# IDS_ADC_SMT.net
KiCad netlist of a schematic drawn in EAGLE
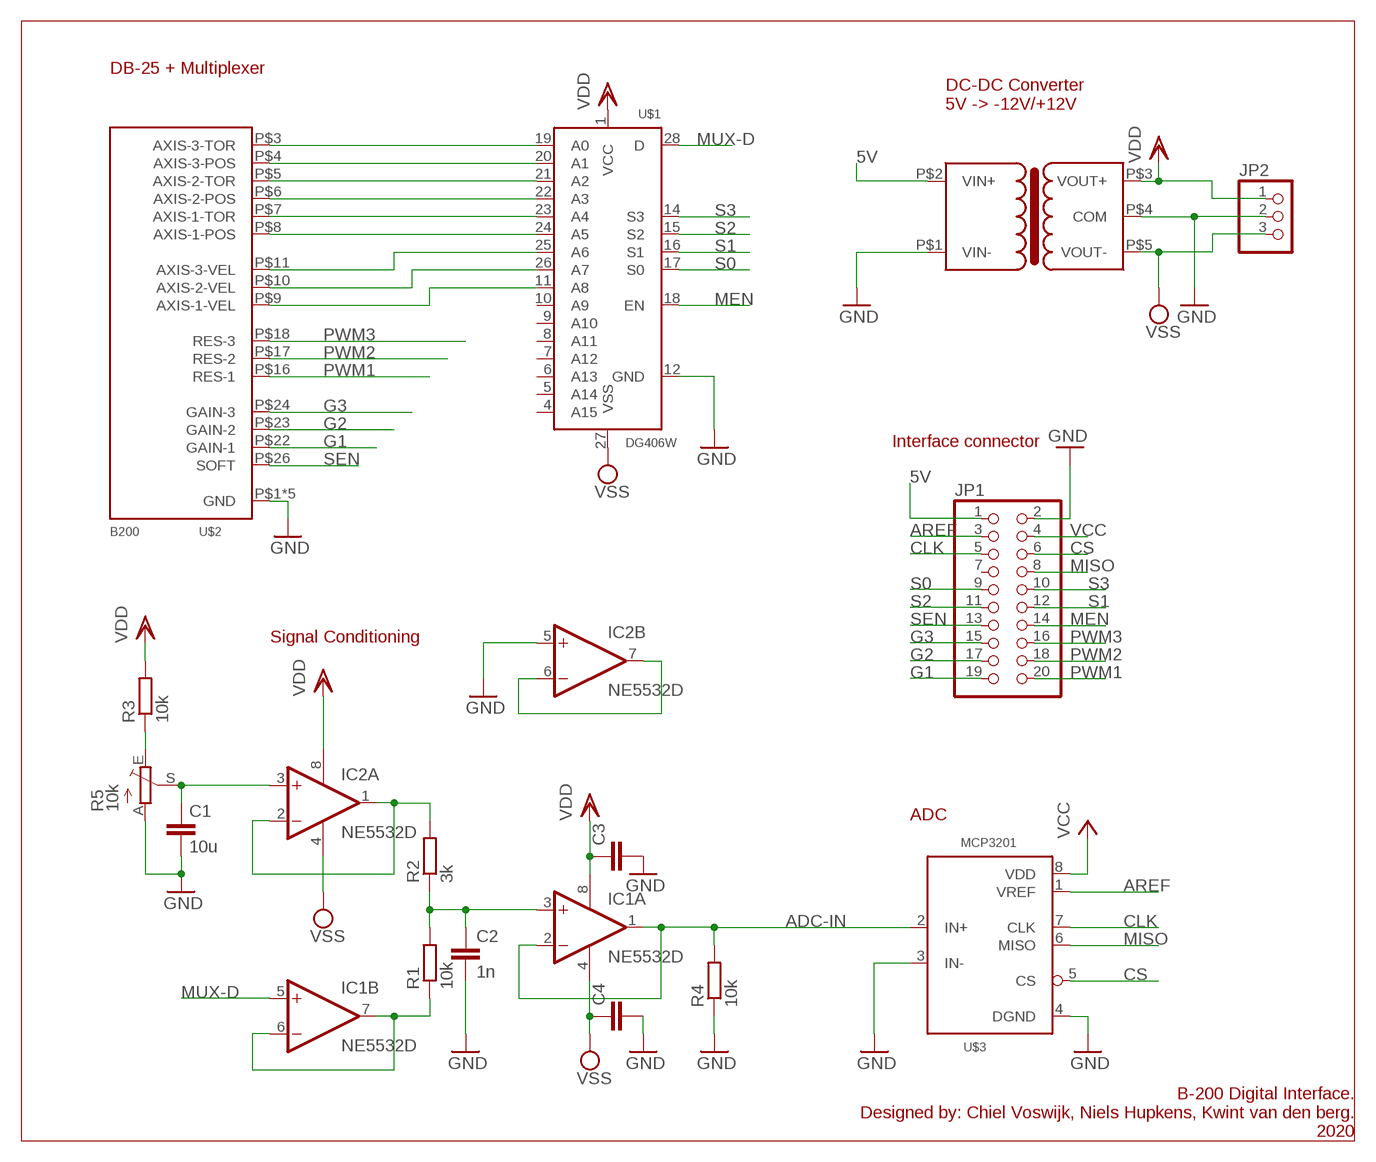
[diagram p0: schematic, sheet 1]

(export (version "E")
  (design (tool "Eeschema 10.0.6"))
  (components
    (comp (ref "C1")
      (value "10u")
      (footprint "eagle-import:C1210")
      (libsource (lib "eagle-import") (part "C-EUC1210"))
    )
    (comp (ref "C2")
      (value "1n")
      (footprint "eagle-import:C0805")
      (libsource (lib "eagle-import") (part "C-EUC0805"))
    )
    (comp (ref "C3")
      (value "C-EUC0805")
      (footprint "eagle-import:C0805")
      (libsource (lib "eagle-import") (part "C-EUC0805"))
    )
    (comp (ref "C4")
      (value "C-EUC0805")
      (footprint "eagle-import:C0805")
      (libsource (lib "eagle-import") (part "C-EUC0805"))
    )
    (comp (ref "IC1")
      (value "NE5532D")
      (footprint "eagle-import:SO08")
      (libsource (lib "eagle-import") (part "NE5532D"))
    )
    (comp (ref "IC2")
      (value "NE5532D")
      (footprint "eagle-import:SO08")
      (libsource (lib "eagle-import") (part "NE5532D"))
    )
    (comp (ref "JP1")
      (value "PINHD-2X10")
      (footprint "eagle-import:2X10")
      (libsource (lib "eagle-import") (part "PINHD-2X10"))
    )
    (comp (ref "JP2")
      (value "PINHD-1X3")
      (footprint "eagle-import:1X03")
      (libsource (lib "eagle-import") (part "PINHD-1X3"))
    )
    (comp (ref "R1")
      (value "10k")
      (footprint "eagle-import:R0805")
      (libsource (lib "eagle-import") (part "R-EU_R0805"))
    )
    (comp (ref "R2")
      (value "3k")
      (footprint "eagle-import:R0805")
      (libsource (lib "eagle-import") (part "R-EU_R0805"))
    )
    (comp (ref "R3")
      (value "10k")
      (footprint "eagle-import:R0805")
      (libsource (lib "eagle-import") (part "R-EU_R0805"))
    )
    (comp (ref "R4")
      (value "10k")
      (footprint "eagle-import:R0805")
      (libsource (lib "eagle-import") (part "R-EU_R0805"))
    )
    (comp (ref "R5")
      (value "10k")
      (footprint "eagle-import:RJ9W")
      (libsource (lib "eagle-import") (part "TRIM_EU-RJ9W"))
    )
    (comp (ref "U$1")
      (value "DG406W")
      (footprint "eagle-import:SO-28W")
      (libsource (lib "eagle-import") (part "DG406W"))
    )
    (comp (ref "U$2")
      (value "B200")
      (footprint "eagle-import:PARALLEL")
      (libsource (lib "eagle-import") (part "B200"))
    )
    (comp (ref "U$3")
      (value "MCP3201")
      (footprint "eagle-import:DIL08")
      (libsource (lib "eagle-import") (part "MCP3201"))
    )
    (comp (ref "U$4")
      (value "TRACO-DR-NE")
      (footprint "eagle-import:TRACO-DCDC-SIP6")
      (libsource (lib "eagle-import") (part "TRACO-DR-NE"))
    )
  )
  (nets
    (net (code "1") (name "/5V") (class "Default")
      (node (ref "JP1") (pin "1") (pinfunction "1_1") (pintype "passive"))
      (node (ref "U$4") (pin "P$2") (pinfunction "VIN+_P$2") (pintype "bidirectional"))
    )
    (net (code "2") (name "/ADC-IN") (class "Default")
      (node (ref "IC1") (pin "1") (pinfunction "OUT_1") (pintype "output"))
      (node (ref "IC1") (pin "2") (pinfunction "-IN_2") (pintype "input"))
      (node (ref "R4") (pin "2") (pinfunction "2_2") (pintype "passive"))
      (node (ref "U$3") (pin "2") (pinfunction "IN+_2") (pintype "input"))
    )
    (net (code "3") (name "/AREF") (class "Default")
      (node (ref "JP1") (pin "3") (pinfunction "3_3") (pintype "passive"))
      (node (ref "U$3") (pin "1") (pinfunction "VREF_1") (pintype "bidirectional"))
    )
    (net (code "4") (name "/CLK") (class "Default")
      (node (ref "JP1") (pin "5") (pinfunction "5_5") (pintype "passive"))
      (node (ref "U$3") (pin "7") (pinfunction "CLK_7") (pintype "bidirectional"))
    )
    (net (code "5") (name "/CS") (class "Default")
      (node (ref "JP1") (pin "6") (pinfunction "6_6") (pintype "passive"))
      (node (ref "U$3") (pin "5") (pinfunction "CS_5") (pintype "bidirectional"))
    )
    (net (code "6") (name "/G1") (class "Default")
      (node (ref "JP1") (pin "19") (pinfunction "19_19") (pintype "passive"))
      (node (ref "U$2") (pin "P$22") (pinfunction "GAIN-1_P$22") (pintype "output"))
    )
    (net (code "7") (name "/G2") (class "Default")
      (node (ref "JP1") (pin "17") (pinfunction "17_17") (pintype "passive"))
      (node (ref "U$2") (pin "P$23") (pinfunction "GAIN-2_P$23") (pintype "output"))
    )
    (net (code "8") (name "/G3") (class "Default")
      (node (ref "JP1") (pin "15") (pinfunction "15_15") (pintype "passive"))
      (node (ref "U$2") (pin "P$24") (pinfunction "GAIN-3_P$24") (pintype "output"))
    )
    (net (code "9") (name "/MEN") (class "Default")
      (node (ref "JP1") (pin "14") (pinfunction "14_14") (pintype "passive"))
      (node (ref "U$1") (pin "18") (pinfunction "EN_18") (pintype "input"))
    )
    (net (code "10") (name "/MISO") (class "Default")
      (node (ref "JP1") (pin "8") (pinfunction "8_8") (pintype "passive"))
      (node (ref "U$3") (pin "6") (pinfunction "MISO_6") (pintype "bidirectional"))
    )
    (net (code "11") (name "/MUX-D") (class "Default")
      (node (ref "IC1") (pin "5") (pinfunction "+IN_5") (pintype "input"))
      (node (ref "U$1") (pin "28") (pinfunction "D_28") (pintype "bidirectional"))
    )
    (net (code "12") (name "/PWM1") (class "Default")
      (node (ref "JP1") (pin "20") (pinfunction "20_20") (pintype "passive"))
      (node (ref "U$2") (pin "P$16") (pinfunction "RES-1_P$16") (pintype "output"))
    )
    (net (code "13") (name "/PWM2") (class "Default")
      (node (ref "JP1") (pin "18") (pinfunction "18_18") (pintype "passive"))
      (node (ref "U$2") (pin "P$17") (pinfunction "RES-2_P$17") (pintype "output"))
    )
    (net (code "14") (name "/PWM3") (class "Default")
      (node (ref "JP1") (pin "16") (pinfunction "16_16") (pintype "passive"))
      (node (ref "U$2") (pin "P$18") (pinfunction "RES-3_P$18") (pintype "output"))
    )
    (net (code "15") (name "/S0") (class "Default")
      (node (ref "JP1") (pin "9") (pinfunction "9_9") (pintype "passive"))
      (node (ref "U$1") (pin "17") (pinfunction "S0_17") (pintype "input"))
    )
    (net (code "16") (name "/S1") (class "Default")
      (node (ref "JP1") (pin "12") (pinfunction "12_12") (pintype "passive"))
      (node (ref "U$1") (pin "16") (pinfunction "S1_16") (pintype "input"))
    )
    (net (code "17") (name "/S2") (class "Default")
      (node (ref "JP1") (pin "11") (pinfunction "11_11") (pintype "passive"))
      (node (ref "U$1") (pin "15") (pinfunction "S2_15") (pintype "input"))
    )
    (net (code "18") (name "/S3") (class "Default")
      (node (ref "JP1") (pin "10") (pinfunction "10_10") (pintype "passive"))
      (node (ref "U$1") (pin "14") (pinfunction "S3_14") (pintype "input"))
    )
    (net (code "19") (name "/SEN") (class "Default")
      (node (ref "JP1") (pin "13") (pinfunction "13_13") (pintype "passive"))
      (node (ref "U$2") (pin "P$26") (pinfunction "SOFT_P$26") (pintype "output"))
    )
    (net (code "20") (name "GND") (class "Default")
      (node (ref "C1") (pin "2") (pinfunction "2_2") (pintype "passive"))
      (node (ref "C2") (pin "2") (pinfunction "2_2") (pintype "passive"))
      (node (ref "C3") (pin "2") (pinfunction "2_2") (pintype "passive"))
      (node (ref "C4") (pin "2") (pinfunction "2_2") (pintype "passive"))
      (node (ref "IC2") (pin "5") (pinfunction "+IN_5") (pintype "input"))
      (node (ref "JP1") (pin "2") (pinfunction "2_2") (pintype "passive"))
      (node (ref "JP2") (pin "2") (pinfunction "2_2") (pintype "passive"))
      (node (ref "R4") (pin "1") (pinfunction "1_1") (pintype "passive"))
      (node (ref "R5") (pin "A") (pinfunction "A_A") (pintype "passive"))
      (node (ref "U$1") (pin "12") (pinfunction "GND_12") (pintype "open_collector"))
      (node (ref "U$2") (pin "P$1") (pinfunction "GND_P$1") (pintype "output"))
      (node (ref "U$2") (pin "P$19") (pinfunction "GND_P$19") (pintype "output"))
      (node (ref "U$2") (pin "P$2") (pinfunction "GND_P$2") (pintype "output"))
      (node (ref "U$2") (pin "P$20") (pinfunction "GND_P$20") (pintype "output"))
      (node (ref "U$2") (pin "P$21") (pinfunction "GND_P$21") (pintype "output"))
      (node (ref "U$3") (pin "3") (pinfunction "IN-_3") (pintype "input"))
      (node (ref "U$3") (pin "4") (pinfunction "DGND_4") (pintype "power_in"))
      (node (ref "U$4") (pin "P$1") (pinfunction "VIN-_P$1") (pintype "bidirectional"))
      (node (ref "U$4") (pin "P$4") (pinfunction "COM_P$4") (pintype "bidirectional"))
    )
    (net (code "21") (name "Net-(IC1A-+IN)") (class "Default")
      (node (ref "C2") (pin "1") (pinfunction "1_1") (pintype "passive"))
      (node (ref "IC1") (pin "3") (pinfunction "+IN_3") (pintype "input"))
      (node (ref "R1") (pin "2") (pinfunction "2_2") (pintype "passive"))
      (node (ref "R2") (pin "1") (pinfunction "1_1") (pintype "passive"))
    )
    (net (code "22") (name "Net-(IC1B--IN)") (class "Default")
      (node (ref "IC1") (pin "6") (pinfunction "-IN_6") (pintype "input"))
      (node (ref "IC1") (pin "7") (pinfunction "OUT_7") (pintype "output"))
      (node (ref "R1") (pin "1") (pinfunction "1_1") (pintype "passive"))
    )
    (net (code "23") (name "Net-(IC2A-+IN)") (class "Default")
      (node (ref "C1") (pin "1") (pinfunction "1_1") (pintype "passive"))
      (node (ref "IC2") (pin "3") (pinfunction "+IN_3") (pintype "input"))
      (node (ref "R5") (pin "S") (pinfunction "S_S") (pintype "passive"))
    )
    (net (code "24") (name "Net-(IC2A--IN)") (class "Default")
      (node (ref "IC2") (pin "1") (pinfunction "OUT_1") (pintype "output"))
      (node (ref "IC2") (pin "2") (pinfunction "-IN_2") (pintype "input"))
      (node (ref "R2") (pin "2") (pinfunction "2_2") (pintype "passive"))
    )
    (net (code "25") (name "Net-(IC2B--IN)") (class "Default")
      (node (ref "IC2") (pin "6") (pinfunction "-IN_6") (pintype "input"))
      (node (ref "IC2") (pin "7") (pinfunction "OUT_7") (pintype "output"))
    )
    (net (code "26") (name "Net-(R3-Pad1)") (class "Default")
      (node (ref "R3") (pin "1") (pinfunction "1_1") (pintype "passive"))
      (node (ref "R5") (pin "E") (pinfunction "E_E") (pintype "passive"))
    )
    (net (code "27") (name "Net-(U$1-A0)") (class "Default")
      (node (ref "U$1") (pin "19") (pinfunction "A0_19") (pintype "bidirectional"))
      (node (ref "U$2") (pin "P$3") (pinfunction "AXIS-3-TOR_P$3") (pintype "output"))
    )
    (net (code "28") (name "Net-(U$1-A1)") (class "Default")
      (node (ref "U$1") (pin "20") (pinfunction "A1_20") (pintype "bidirectional"))
      (node (ref "U$2") (pin "P$4") (pinfunction "AXIS-3-POS_P$4") (pintype "output"))
    )
    (net (code "29") (name "Net-(U$1-A2)") (class "Default")
      (node (ref "U$1") (pin "21") (pinfunction "A2_21") (pintype "bidirectional"))
      (node (ref "U$2") (pin "P$5") (pinfunction "AXIS-2-TOR_P$5") (pintype "output"))
    )
    (net (code "30") (name "Net-(U$1-A3)") (class "Default")
      (node (ref "U$1") (pin "22") (pinfunction "A3_22") (pintype "bidirectional"))
      (node (ref "U$2") (pin "P$6") (pinfunction "AXIS-2-POS_P$6") (pintype "output"))
    )
    (net (code "31") (name "Net-(U$1-A4)") (class "Default")
      (node (ref "U$1") (pin "23") (pinfunction "A4_23") (pintype "bidirectional"))
      (node (ref "U$2") (pin "P$7") (pinfunction "AXIS-1-TOR_P$7") (pintype "output"))
    )
    (net (code "32") (name "Net-(U$1-A5)") (class "Default")
      (node (ref "U$1") (pin "24") (pinfunction "A5_24") (pintype "bidirectional"))
      (node (ref "U$2") (pin "P$8") (pinfunction "AXIS-1-POS_P$8") (pintype "output"))
    )
    (net (code "33") (name "Net-(U$1-A6)") (class "Default")
      (node (ref "U$1") (pin "25") (pinfunction "A6_25") (pintype "bidirectional"))
      (node (ref "U$2") (pin "P$11") (pinfunction "AXIS-3-VEL_P$11") (pintype "output"))
    )
    (net (code "34") (name "Net-(U$1-A7)") (class "Default")
      (node (ref "U$1") (pin "26") (pinfunction "A7_26") (pintype "bidirectional"))
      (node (ref "U$2") (pin "P$10") (pinfunction "AXIS-2-VEL_P$10") (pintype "output"))
    )
    (net (code "35") (name "Net-(U$1-A8)") (class "Default")
      (node (ref "U$1") (pin "11") (pinfunction "A8_11") (pintype "bidirectional"))
      (node (ref "U$2") (pin "P$9") (pinfunction "AXIS-1-VEL_P$9") (pintype "output"))
    )
    (net (code "36") (name "VCC") (class "Default")
      (node (ref "JP1") (pin "4") (pinfunction "4_4") (pintype "passive"))
      (node (ref "U$3") (pin "8") (pinfunction "VDD_8") (pintype "power_in"))
    )
    (net (code "37") (name "VDD") (class "Default")
      (node (ref "C3") (pin "1") (pinfunction "1_1") (pintype "passive"))
      (node (ref "IC1") (pin "8") (pinfunction "V+_8") (pintype "power_in"))
      (node (ref "IC2") (pin "8") (pinfunction "V+_8") (pintype "power_in"))
      (node (ref "JP2") (pin "1") (pinfunction "1_1") (pintype "passive"))
      (node (ref "R3") (pin "2") (pinfunction "2_2") (pintype "passive"))
      (node (ref "U$1") (pin "1") (pinfunction "VCC_1") (pintype "power_in"))
      (node (ref "U$4") (pin "P$3") (pinfunction "VOUT+_P$3") (pintype "bidirectional"))
    )
    (net (code "38") (name "VSS") (class "Default")
      (node (ref "C4") (pin "1") (pinfunction "1_1") (pintype "passive"))
      (node (ref "IC1") (pin "4") (pinfunction "V-_4") (pintype "power_in"))
      (node (ref "IC2") (pin "4") (pinfunction "V-_4") (pintype "power_in"))
      (node (ref "JP2") (pin "3") (pinfunction "3_3") (pintype "passive"))
      (node (ref "U$1") (pin "27") (pinfunction "VSS_27") (pintype "open_collector"))
      (node (ref "U$4") (pin "P$5") (pinfunction "VOUT-_P$5") (pintype "bidirectional"))
    )
    (net (code "39") (name "unconnected-(JP1-Pad7)") (class "Default")
      (node (ref "JP1") (pin "7") (pinfunction "7_7") (pintype "passive"))
    )
    (net (code "40") (name "unconnected-(U$1-A9-Pad10)") (class "Default")
      (node (ref "U$1") (pin "10") (pinfunction "A9_10") (pintype "bidirectional"))
    )
    (net (code "41") (name "unconnected-(U$1-A10-Pad9)") (class "Default")
      (node (ref "U$1") (pin "9") (pinfunction "A10_9") (pintype "bidirectional"))
    )
    (net (code "42") (name "unconnected-(U$1-A11-Pad8)") (class "Default")
      (node (ref "U$1") (pin "8") (pinfunction "A11_8") (pintype "bidirectional"))
    )
    (net (code "43") (name "unconnected-(U$1-A12-Pad7)") (class "Default")
      (node (ref "U$1") (pin "7") (pinfunction "A12_7") (pintype "bidirectional"))
    )
    (net (code "44") (name "unconnected-(U$1-A13-Pad6)") (class "Default")
      (node (ref "U$1") (pin "6") (pinfunction "A13_6") (pintype "bidirectional"))
    )
    (net (code "45") (name "unconnected-(U$1-A14-Pad5)") (class "Default")
      (node (ref "U$1") (pin "5") (pinfunction "A14_5") (pintype "bidirectional"))
    )
    (net (code "46") (name "unconnected-(U$1-A15-Pad4)") (class "Default")
      (node (ref "U$1") (pin "4") (pinfunction "A15_4") (pintype "bidirectional"))
    )
  )
)
